# SCH_Flipper-FN.net
KiCad netlist of a schematic drawn in EasyEDA
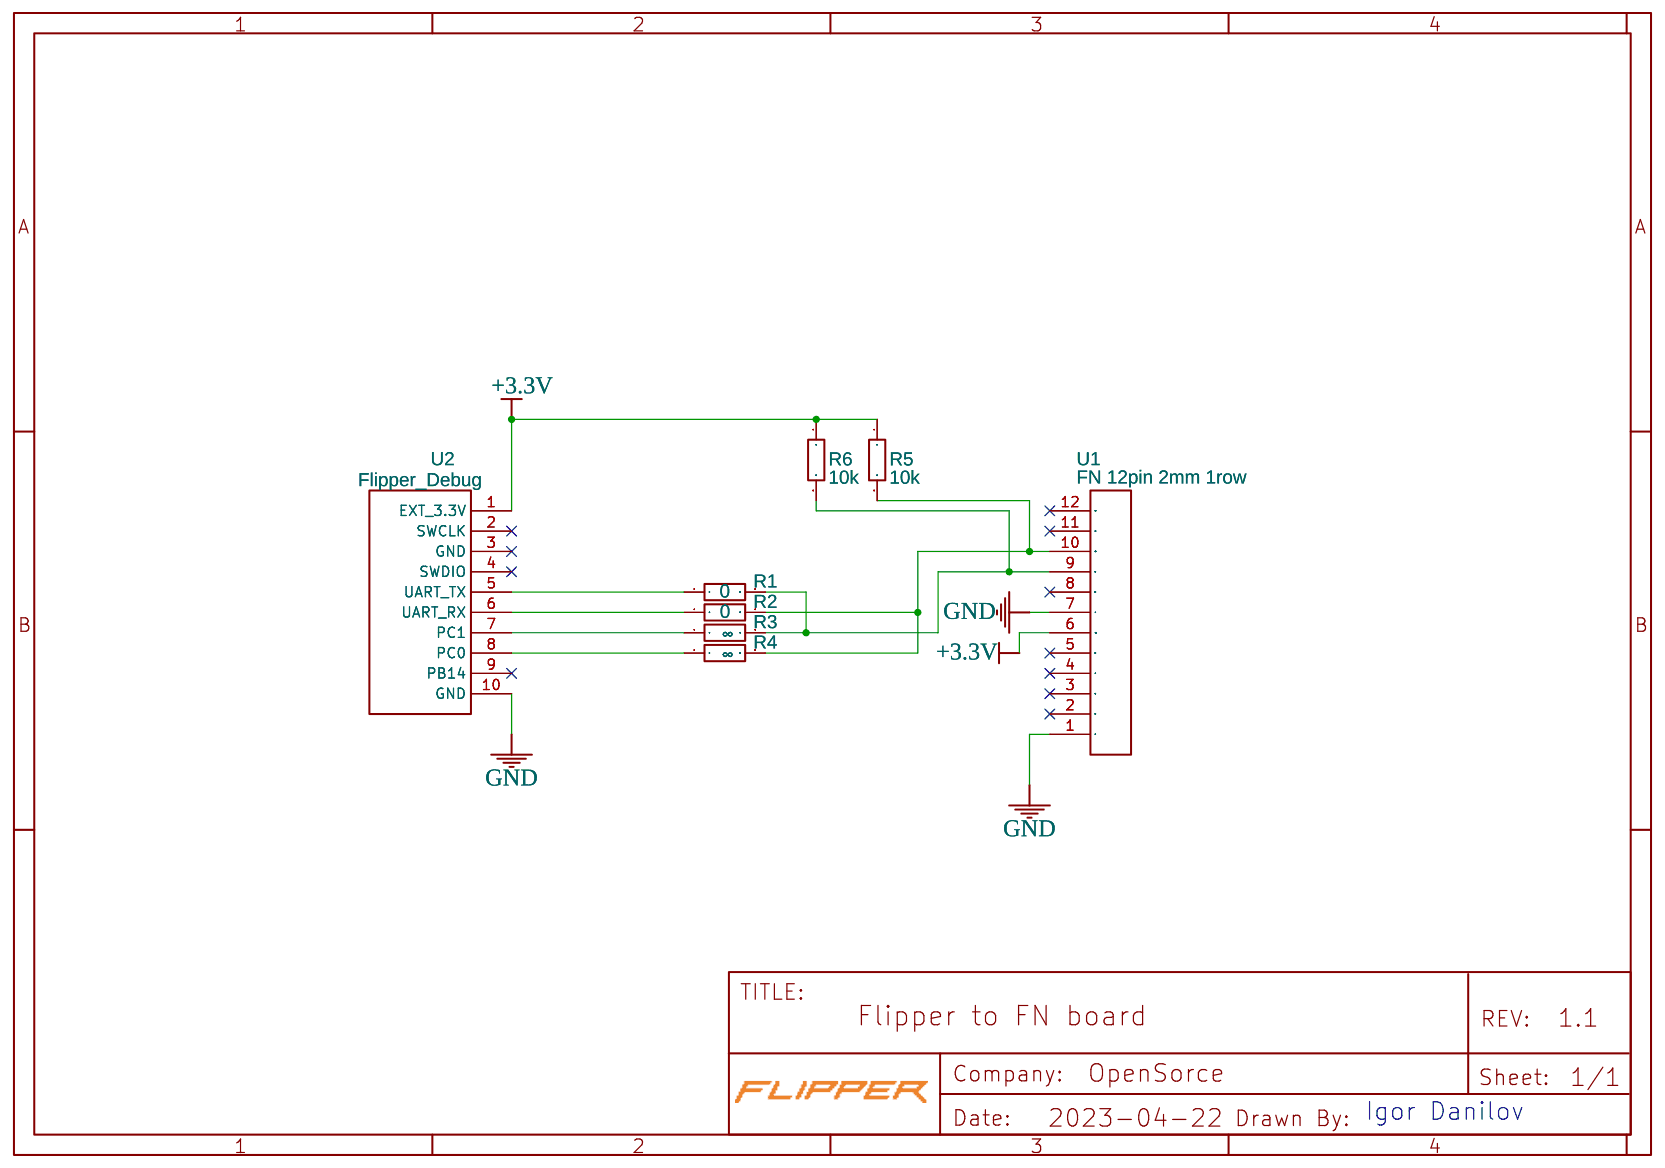
[diagram p0: schematic sheet]

(export (version "E")
  (design (tool "Eeschema 10.0.6"))
  (components
    (comp (ref "R1")
      (value "0")
      (fields (field (name "Manufacturer Part") "CMFB103F3970") (field (name "Manufacturer") "Shiheng"))
      (libsource (lib "") (part "SMD_Resistor"))
    )
    (comp (ref "R2")
      (value "0")
      (fields (field (name "Manufacturer Part") "CMFB103F3970") (field (name "Manufacturer") "Shiheng"))
      (libsource (lib "") (part "SMD_Resistor"))
    )
    (comp (ref "R3")
      (value "∞")
      (fields (field (name "Manufacturer Part") "CMFB103F3970") (field (name "Manufacturer") "Shiheng"))
      (libsource (lib "") (part "SMD_Resistor"))
    )
    (comp (ref "R4")
      (value "∞")
      (fields (field (name "Manufacturer Part") "CMFB103F3970") (field (name "Manufacturer") "Shiheng"))
      (libsource (lib "") (part "SMD_Resistor"))
    )
    (comp (ref "R5")
      (value "10k")
      (fields (field (name "Manufacturer Part") "CMFB103F3970") (field (name "Manufacturer") "Shiheng"))
      (libsource (lib "") (part "SMD_Resistor_1"))
    )
    (comp (ref "R6")
      (value "10k")
      (fields (field (name "Manufacturer Part") "CMFB103F3970") (field (name "Manufacturer") "Shiheng"))
      (libsource (lib "") (part "SMD_Resistor_1"))
    )
    (comp (ref "U1") (value "FN 12pin 2mm 1row") (libsource (lib "") (part "12pin 2mm 1row")))
    (comp (ref "U2") (value "Flipper_Debug") (libsource (lib "") (part "Flipper_Debug")))
  )
  (nets
    (net (code "1") (name "+3.3V") (class "Default")
      (node (ref "R5") (pin "1") (pinfunction "1_1") (pintype "input"))
      (node (ref "R6") (pin "1") (pinfunction "1_1") (pintype "input"))
      (node (ref "U1") (pin "6") (pinfunction "+3.3V_6") (pintype "unspecified"))
      (node (ref "U2") (pin "1") (pinfunction "EXT_3.3V_1") (pintype "unspecified"))
    )
    (net (code "2") (name "GND") (class "Default")
      (node (ref "U1") (pin "1") (pinfunction "1_1") (pintype "unspecified"))
      (node (ref "U1") (pin "7") (pinfunction "7_7") (pintype "unspecified"))
      (node (ref "U2") (pin "10") (pinfunction "GND_10") (pintype "unspecified"))
    )
    (net (code "3") (name "Net-(R1-Pad2)") (class "Default")
      (node (ref "R1") (pin "2") (pinfunction "2_2") (pintype "input"))
      (node (ref "R3") (pin "2") (pinfunction "2_2") (pintype "input"))
      (node (ref "R6") (pin "2") (pinfunction "2_2") (pintype "input"))
      (node (ref "U1") (pin "9") (pinfunction "9_9") (pintype "unspecified"))
    )
    (net (code "4") (name "Net-(R2-Pad2)") (class "Default")
      (node (ref "R2") (pin "2") (pinfunction "2_2") (pintype "input"))
      (node (ref "R4") (pin "2") (pinfunction "2_2") (pintype "input"))
      (node (ref "R5") (pin "2") (pinfunction "2_2") (pintype "input"))
      (node (ref "U1") (pin "10") (pinfunction "10_10") (pintype "unspecified"))
    )
    (net (code "5") (name "Net-(U2-PC0)") (class "Default")
      (node (ref "R4") (pin "1") (pinfunction "1_1") (pintype "input"))
      (node (ref "U2") (pin "8") (pinfunction "PC0_8") (pintype "unspecified"))
    )
    (net (code "6") (name "Net-(U2-PC1)") (class "Default")
      (node (ref "R3") (pin "1") (pinfunction "1_1") (pintype "input"))
      (node (ref "U2") (pin "7") (pinfunction "PC1_7") (pintype "unspecified"))
    )
    (net (code "7") (name "Net-(U2-UART_RX)") (class "Default")
      (node (ref "R2") (pin "1") (pinfunction "1_1") (pintype "input"))
      (node (ref "U2") (pin "6") (pinfunction "UART_RX_6") (pintype "unspecified"))
    )
    (net (code "8") (name "Net-(U2-UART_TX)") (class "Default")
      (node (ref "R1") (pin "1") (pinfunction "1_1") (pintype "input"))
      (node (ref "U2") (pin "5") (pinfunction "UART_TX_5") (pintype "unspecified"))
    )
    (net (code "9") (name "unconnected-(U1-Pad2)") (class "Default")
      (node (ref "U1") (pin "2") (pinfunction "2_2") (pintype "unspecified+no_connect"))
    )
    (net (code "10") (name "unconnected-(U1-Pad3)") (class "Default")
      (node (ref "U1") (pin "3") (pinfunction "3_3") (pintype "unspecified+no_connect"))
    )
    (net (code "11") (name "unconnected-(U1-Pad4)") (class "Default")
      (node (ref "U1") (pin "4") (pinfunction "4_4") (pintype "unspecified+no_connect"))
    )
    (net (code "12") (name "unconnected-(U1-Pad5)") (class "Default")
      (node (ref "U1") (pin "5") (pinfunction "5_5") (pintype "unspecified+no_connect"))
    )
    (net (code "13") (name "unconnected-(U1-Pad8)") (class "Default")
      (node (ref "U1") (pin "8") (pinfunction "8_8") (pintype "unspecified+no_connect"))
    )
    (net (code "14") (name "unconnected-(U1-Pad11)") (class "Default")
      (node (ref "U1") (pin "11") (pinfunction "11_11") (pintype "unspecified+no_connect"))
    )
    (net (code "15") (name "unconnected-(U1-Pad12)") (class "Default")
      (node (ref "U1") (pin "12") (pinfunction "12_12") (pintype "unspecified+no_connect"))
    )
    (net (code "16") (name "unconnected-(U2-GND-Pad3)") (class "Default")
      (node (ref "U2") (pin "3") (pinfunction "GND_3") (pintype "unspecified+no_connect"))
    )
    (net (code "17") (name "unconnected-(U2-PB14-Pad9)") (class "Default")
      (node (ref "U2") (pin "9") (pinfunction "PB14_9") (pintype "unspecified+no_connect"))
    )
    (net (code "18") (name "unconnected-(U2-SWCLK-Pad2)") (class "Default")
      (node (ref "U2") (pin "2") (pinfunction "SWCLK_2") (pintype "unspecified+no_connect"))
    )
    (net (code "19") (name "unconnected-(U2-SWDIO-Pad4)") (class "Default")
      (node (ref "U2") (pin "4") (pinfunction "SWDIO_4") (pintype "unspecified+no_connect"))
    )
  )
)
